# 03-ZYNQ_BANK_500.net
KiCad netlist of a schematic drawn in Altium Designer
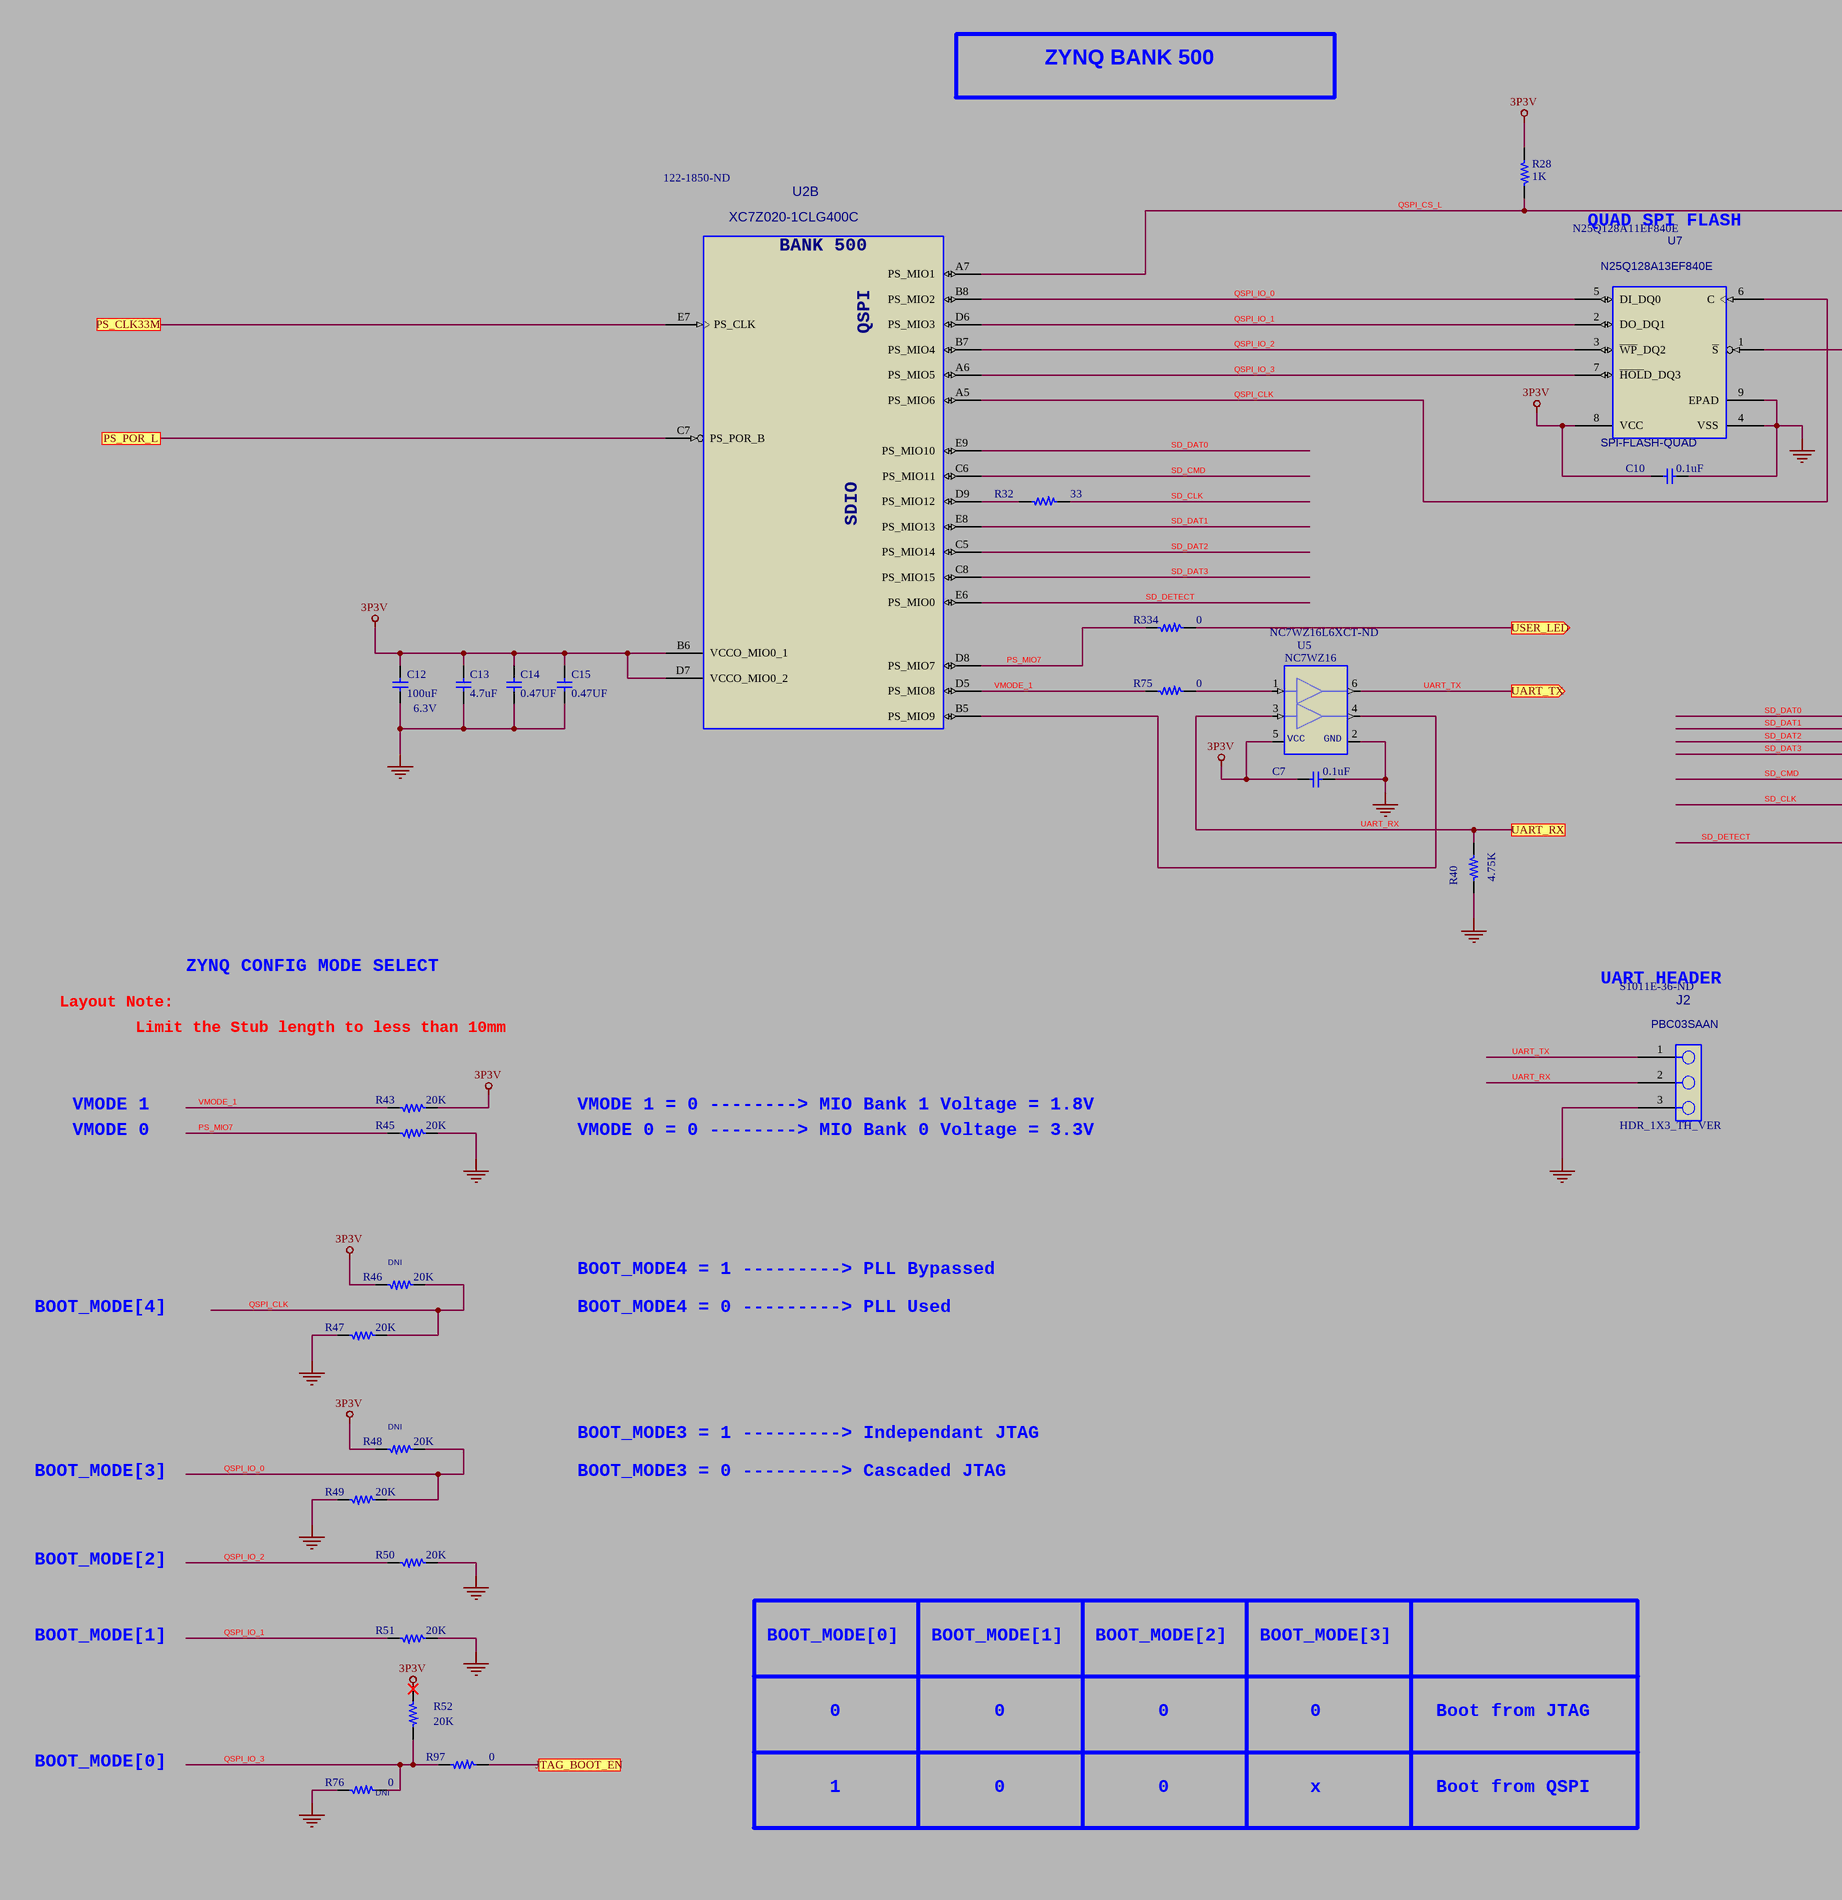
[diagram p0: 03-ZYNQ BANK 500.SchDoc, left]
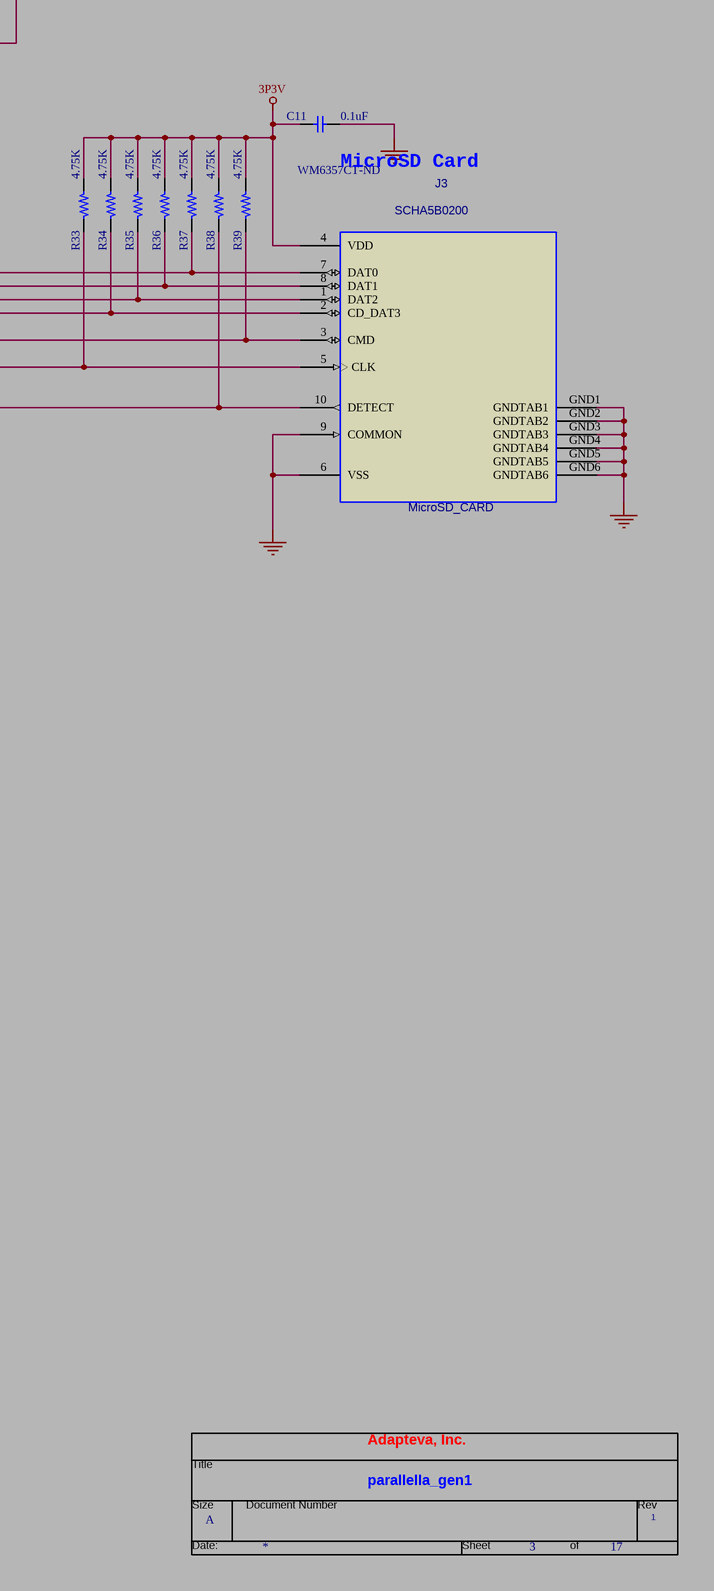
[diagram p1: 03-ZYNQ BANK 500.SchDoc, right]

(export (version "E")
  (design (tool "Eeschema 10.0.6"))
  (components
    (comp (ref "C7")
      (value "0.1uF")
      (footprint "C0402")
      (description "CAP, 0402, 0.1UF, X5R, 35V")
      (fields (field (name "MFG PART NO") "GMK105BJ104KV-F") (field (name "MFG") "TAIYO YUDEN"))
      (libsource (lib "*") (part "CAP0402_0P1UF_X5R_35V"))
    )
    (comp (ref "C10")
      (value "0.1uF")
      (footprint "C0402")
      (description "CAP, 0402, 0.1UF, X5R, 35V")
      (fields (field (name "MFG PART NO") "GMK105BJ104KV-F") (field (name "MFG") "TAIYO YUDEN"))
      (libsource (lib "*") (part "CAP0402_0P1UF_X5R_35V"))
    )
    (comp (ref "C11")
      (value "0.1uF")
      (footprint "C0402")
      (description "CAP, 0402, 0.1UF, X5R, 35V")
      (fields (field (name "MFG PART NO") "GMK105BJ104KV-F") (field (name "MFG") "TAIYO YUDEN"))
      (libsource (lib "*") (part "CAP0402_0P1UF_X5R_35V"))
    )
    (comp (ref "C12")
      (value "100uF")
      (footprint "C1210")
      (description "CAP, 1210, 100UF, X5R, 6.3V, LOW ESR")
      (fields
        (field (name "VOLTAGE") "6.3V")
        (field (name "MFG PART NO") "GRM32ER60J107ME20L")
        (field (name "MFG") "MURATA")
      )
      (libsource (lib "*") (part "CAP1210_100UF_X5R_LOESR"))
    )
    (comp (ref "C13")
      (value "4.7uF")
      (footprint "C0402")
      (description "CAP, 0402, 4.7UF, X5R, 6.3V")
      (fields (field (name "MFG PART NO") "C1005X5R0J475K") (field (name "MFG") "TDK"))
      (libsource (lib "*") (part "CAP0402_4P7UF_X5R"))
    )
    (comp (ref "C14")
      (value "0.47UF")
      (footprint "C0402")
      (description "CAP, 0402, 0.47UF, X5R, 16V")
      (fields (field (name "MFG") "TDK") (field (name "MFG PART NO") "C1005X5R1C474K"))
      (libsource (lib "*") (part "CAP0402_0P47UF_X5R"))
    )
    (comp (ref "C15")
      (value "0.47UF")
      (footprint "C0402")
      (description "CAP, 0402, 0.47UF, X5R, 16V")
      (fields (field (name "MFG") "TDK") (field (name "MFG PART NO") "C1005X5R1C474K"))
      (libsource (lib "*") (part "CAP0402_0P47UF_X5R"))
    )
    (comp (ref "J2")
      (value "HDR_1X3_TH_VER")
      (footprint "HDR_1X3_TH_VER")
      (description "HDR, 1ROW, 3POS, VERT, TH, 1X3, 0.100 PITCH")
      (fields
        (field (name "VENDOR PN") "PBC03SAAN")
        (field (name "MFG") "SULLINS")
        (field (name "MFG PART NO") "PBC36SAAN")
        (field (name "SUPPLIER PART NUMBER 1") "S1011E-36-ND")
      )
      (libsource (lib "*") (part "HDR_1X3_TH_VER_0.1P"))
    )
    (comp (ref "J3")
      (value "MicroSD_CARD")
      (footprint "SDMICRO_8PIN_REV_15SQX1P51MMH")
      (description "CONN, MICRO SD CARD, PUSH-PUSH")
      (fields
        (field (name "VENDOR PN") "SCHA5B0200")
        (field (name "MFG") "ALPS")
        (field (name "SUPPLIER PART NUMBER 1") "WM6357CT-ND")
      )
      (libsource (lib "*") (part "CONN_MICROSD_CARD"))
    )
    (comp (ref "R28")
      (value "1K")
      (footprint "R0402")
      (description "RES, 0402, 1K")
      (fields (field (name "MFG") "VISHAY") (field (name "MFG PART NO") "CRCW04021K00FKED"))
      (libsource (lib "*") (part "RES0402_1K"))
    )
    (comp (ref "R32")
      (value "33")
      (footprint "R0402")
      (description "RES, 0402, 33, 1%")
      (fields (field (name "MFG") "VISHAY") (field (name "MFG PART NO") "CRCW040233R0FKED"))
      (libsource (lib "*") (part "RES0402_33"))
    )
    (comp (ref "R33")
      (value "4.75K")
      (footprint "R0402")
      (description "RES, 0402, 4.75K, 1%")
      (fields (field (name "MFG") "VISHAY") (field (name "MFG PART NO") "CRCW04024K75FKED"))
      (libsource (lib "*") (part "RES0402_4K75"))
    )
    (comp (ref "R34")
      (value "4.75K")
      (footprint "R0402")
      (description "RES, 0402, 4.75K, 1%")
      (fields (field (name "MFG") "VISHAY") (field (name "MFG PART NO") "CRCW04024K75FKED"))
      (libsource (lib "*") (part "RES0402_4K75"))
    )
    (comp (ref "R35")
      (value "4.75K")
      (footprint "R0402")
      (description "RES, 0402, 4.75K, 1%")
      (fields (field (name "MFG") "VISHAY") (field (name "MFG PART NO") "CRCW04024K75FKED"))
      (libsource (lib "*") (part "RES0402_4K75"))
    )
    (comp (ref "R36")
      (value "4.75K")
      (footprint "R0402")
      (description "RES, 0402, 4.75K, 1%")
      (fields (field (name "MFG") "VISHAY") (field (name "MFG PART NO") "CRCW04024K75FKED"))
      (libsource (lib "*") (part "RES0402_4K75"))
    )
    (comp (ref "R37")
      (value "4.75K")
      (footprint "R0402")
      (description "RES, 0402, 4.75K, 1%")
      (fields (field (name "MFG") "VISHAY") (field (name "MFG PART NO") "CRCW04024K75FKED"))
      (libsource (lib "*") (part "RES0402_4K75"))
    )
    (comp (ref "R38")
      (value "4.75K")
      (footprint "R0402")
      (description "RES, 0402, 4.75K, 1%")
      (fields (field (name "MFG") "VISHAY") (field (name "MFG PART NO") "CRCW04024K75FKED"))
      (libsource (lib "*") (part "RES0402_4K75"))
    )
    (comp (ref "R39")
      (value "4.75K")
      (footprint "R0402")
      (description "RES, 0402, 4.75K, 1%")
      (fields (field (name "MFG") "VISHAY") (field (name "MFG PART NO") "CRCW04024K75FKED"))
      (libsource (lib "*") (part "RES0402_4K75"))
    )
    (comp (ref "R40")
      (value "4.75K")
      (footprint "R0402")
      (description "RES, 0402, 4.75K, 1%")
      (fields (field (name "MFG") "VISHAY") (field (name "MFG PART NO") "CRCW04024K75FKED"))
      (libsource (lib "*") (part "RES0402_4K75"))
    )
    (comp (ref "R43")
      (value "20K")
      (footprint "R0402")
      (description "RES, 0402, 20K")
      (fields (field (name "MFG PART NO") "CRCW040220K0FKED") (field (name "MFG") "VISHAY"))
      (libsource (lib "*") (part "RES0402_20K"))
    )
    (comp (ref "R45")
      (value "20K")
      (footprint "R0402")
      (description "RES, 0402, 20K")
      (fields (field (name "MFG PART NO") "CRCW040220K0FKED") (field (name "MFG") "VISHAY"))
      (libsource (lib "*") (part "RES0402_20K"))
    )
    (comp (ref "R46")
      (value "20K")
      (footprint "R0402")
      (description "RES, 0402, 20K")
      (fields
        (field (name "MFG PART NO") "CRCW040220K0FKED")
        (field (name "MFG") "VISHAY")
        (field (name "INSTALL") "DNI")
      )
      (libsource (lib "*") (part "RES0402_20K"))
    )
    (comp (ref "R47")
      (value "20K")
      (footprint "R0402")
      (description "RES, 0402, 20K")
      (fields (field (name "MFG PART NO") "CRCW040220K0FKED") (field (name "MFG") "VISHAY"))
      (libsource (lib "*") (part "RES0402_20K"))
    )
    (comp (ref "R48")
      (value "20K")
      (footprint "R0402")
      (description "RES, 0402, 20K")
      (fields
        (field (name "MFG PART NO") "CRCW040220K0FKED")
        (field (name "MFG") "VISHAY")
        (field (name "INSTALL") "DNI")
      )
      (libsource (lib "*") (part "RES0402_20K"))
    )
    (comp (ref "R49")
      (value "20K")
      (footprint "R0402")
      (description "RES, 0402, 20K")
      (fields (field (name "MFG PART NO") "CRCW040220K0FKED") (field (name "MFG") "VISHAY"))
      (libsource (lib "*") (part "RES0402_20K"))
    )
    (comp (ref "R50")
      (value "20K")
      (footprint "R0402")
      (description "RES, 0402, 20K")
      (fields (field (name "MFG PART NO") "CRCW040220K0FKED") (field (name "MFG") "VISHAY"))
      (libsource (lib "*") (part "RES0402_20K"))
    )
    (comp (ref "R51")
      (value "20K")
      (footprint "R0402")
      (description "RES, 0402, 20K")
      (fields (field (name "MFG PART NO") "CRCW040220K0FKED") (field (name "MFG") "VISHAY"))
      (libsource (lib "*") (part "RES0402_20K"))
    )
    (comp (ref "R52")
      (value "20K")
      (footprint "R0402")
      (description "RES, 0402, 20K")
      (fields (field (name "MFG PART NO") "CRCW040220K0FKED") (field (name "MFG") "VISHAY"))
      (libsource (lib "*") (part "RES0402_20K"))
    )
    (comp (ref "R75")
      (value "0")
      (footprint "R0402")
      (description "RES, 0402, 0 OHM, 1%")
      (fields (field (name "MFG") "VISHAY") (field (name "MFG PART NO") "CRCW04020000Z0ED"))
      (libsource (lib "*") (part "RES0402_0"))
    )
    (comp (ref "R76")
      (value "0")
      (footprint "R0402")
      (description "RES, 0402, 0 OHM, 1%")
      (fields
        (field (name "MFG") "VISHAY")
        (field (name "MFG PART NO") "CRCW04020000Z0ED")
        (field (name "INSTALL") "DNI")
      )
      (libsource (lib "*") (part "RES0402_0"))
    )
    (comp (ref "R97")
      (value "0")
      (footprint "R0402")
      (description "RES, 0402, 0 OHM, 1%")
      (fields (field (name "MFG") "VISHAY") (field (name "MFG PART NO") "CRCW04020000Z0ED"))
      (libsource (lib "*") (part "RES0402_0"))
    )
    (comp (ref "R334")
      (value "0")
      (footprint "R0402")
      (description "RES, 0402, 0 OHM, 1%")
      (fields (field (name "MFG") "VISHAY") (field (name "MFG PART NO") "CRCW04020000Z0ED"))
      (libsource (lib "*") (part "RES0402_0"))
    )
    (comp (ref "U2")
      (value "7Z020-CLG400")
      (footprint "CBGA400_17SQ_1P6H_P8MMP")
      (description "IC, EPP, XILINX, ZYNQ, 7Z020, CLG400")
      (fields
        (field (name "VENDOR PN") "XC7Z020-1CLG400C")
        (field (name "SUPPLIER PART NUMBER 1") "122-1850-ND")
      )
      (libsource (lib "*") (part "ZYNQ_7Z020_CLG400"))
    )
    (comp (ref "U5")
      (value "NC7WZ16")
      (footprint "SC_70_6PSMT")
      (fields
        (field (name "MFG PART NO") "NC7WZ16P6X")
        (field (name "MFG") "FAIRCHILD")
        (field (name "SUPPLIER PART NUMBER 1") "NC7WZ16L6XCT-ND")
      )
      (libsource (lib "*") (part "NC7WZ16"))
    )
    (comp (ref "U7")
      (value "SPI-FLASH-QUAD")
      (footprint "VPDFN-8_6X8XP85H_1P27MMP")
      (description "SPI FLASH, QUAD, 128M-BIT, VPDFN8, 1.8V")
      (fields
        (field (name "MFG") "MICRON")
        (field (name "MFG PART NO") "N25Q128A11EF840E")
        (field (name "VENDOR PN") "N25Q128A13EF840E")
        (field (name "SUPPLIER PART NUMBER 1") "N25Q128A11EF840E")
      )
      (libsource (lib "*") (part "IC_SPI_FLASH_QUAD_128Mb"))
    )
  )
  (nets
    (net (code "1") (name "/JTAG_BOOT_EN") (class "Default")
      (node (ref "R97") (pin "2") (pinfunction "2_2") (pintype "passive"))
    )
    (net (code "2") (name "/PS_CLK33M") (class "Default")
      (node (ref "U2") (pin "E7") (pinfunction "PS_CLK_E7") (pintype "input"))
    )
    (net (code "3") (name "/PS_MIO7") (class "Default")
      (node (ref "R334") (pin "1") (pinfunction "1_1") (pintype "passive"))
      (node (ref "R45") (pin "2") (pinfunction "2_2") (pintype "passive"))
      (node (ref "U2") (pin "D8") (pinfunction "PS_MIO7_D8") (pintype "bidirectional"))
    )
    (net (code "4") (name "/PS_POR_L") (class "Default")
      (node (ref "U2") (pin "C7") (pinfunction "PS_POR_B_C7") (pintype "input"))
    )
    (net (code "5") (name "/QSPI_CLK") (class "Default")
      (node (ref "R46") (pin "1") (pinfunction "1_1") (pintype "passive"))
      (node (ref "R47") (pin "1") (pinfunction "1_1") (pintype "passive"))
      (node (ref "U2") (pin "A5") (pinfunction "PS_MIO6_A5") (pintype "bidirectional"))
      (node (ref "U7") (pin "6") (pinfunction "C_6") (pintype "input"))
    )
    (net (code "6") (name "/QSPI_CS_L") (class "Default")
      (node (ref "R28") (pin "2") (pinfunction "2_2") (pintype "passive"))
      (node (ref "U2") (pin "A7") (pinfunction "PS_MIO1_A7") (pintype "bidirectional"))
      (node (ref "U7") (pin "1") (pinfunction "~{S}_1") (pintype "input"))
    )
    (net (code "7") (name "/QSPI_IO_0") (class "Default")
      (node (ref "R48") (pin "1") (pinfunction "1_1") (pintype "passive"))
      (node (ref "R49") (pin "1") (pinfunction "1_1") (pintype "passive"))
      (node (ref "U2") (pin "B8") (pinfunction "PS_MIO2_B8") (pintype "bidirectional"))
      (node (ref "U7") (pin "5") (pinfunction "DI_DQ0_5") (pintype "bidirectional"))
    )
    (net (code "8") (name "/QSPI_IO_1") (class "Default")
      (node (ref "R51") (pin "2") (pinfunction "2_2") (pintype "passive"))
      (node (ref "U2") (pin "D6") (pinfunction "PS_MIO3_D6") (pintype "bidirectional"))
      (node (ref "U7") (pin "2") (pinfunction "DO_DQ1_2") (pintype "bidirectional"))
    )
    (net (code "9") (name "/QSPI_IO_2") (class "Default")
      (node (ref "R50") (pin "2") (pinfunction "2_2") (pintype "passive"))
      (node (ref "U2") (pin "B7") (pinfunction "PS_MIO4_B7") (pintype "bidirectional"))
      (node (ref "U7") (pin "3") (pinfunction "~{WP}_DQ2_3") (pintype "bidirectional"))
    )
    (net (code "10") (name "/QSPI_IO_3") (class "Default")
      (node (ref "R52") (pin "2") (pinfunction "2_2") (pintype "passive"))
      (node (ref "R76") (pin "2") (pinfunction "2_2") (pintype "passive"))
      (node (ref "R97") (pin "1") (pinfunction "1_1") (pintype "passive"))
      (node (ref "U2") (pin "A6") (pinfunction "PS_MIO5_A6") (pintype "bidirectional"))
      (node (ref "U7") (pin "7") (pinfunction "~{HOL}D_DQ3_7") (pintype "bidirectional"))
    )
    (net (code "11") (name "/SD_CLK") (class "Default")
      (node (ref "J3") (pin "5") (pinfunction "CLK_5") (pintype "input"))
      (node (ref "R32") (pin "2") (pinfunction "2_2") (pintype "passive"))
      (node (ref "R33") (pin "1") (pinfunction "1_1") (pintype "passive"))
    )
    (net (code "12") (name "/SD_CMD") (class "Default")
      (node (ref "J3") (pin "3") (pinfunction "CMD_3") (pintype "bidirectional"))
      (node (ref "R39") (pin "1") (pinfunction "1_1") (pintype "passive"))
      (node (ref "U2") (pin "C6") (pinfunction "PS_MIO11_C6") (pintype "bidirectional"))
    )
    (net (code "13") (name "/SD_DAT0") (class "Default")
      (node (ref "J3") (pin "7") (pinfunction "DAT0_7") (pintype "bidirectional"))
      (node (ref "R37") (pin "1") (pinfunction "1_1") (pintype "passive"))
      (node (ref "U2") (pin "E9") (pinfunction "PS_MIO10_E9") (pintype "bidirectional"))
    )
    (net (code "14") (name "/SD_DAT1") (class "Default")
      (node (ref "J3") (pin "8") (pinfunction "DAT1_8") (pintype "bidirectional"))
      (node (ref "R36") (pin "1") (pinfunction "1_1") (pintype "passive"))
      (node (ref "U2") (pin "E8") (pinfunction "PS_MIO13_E8") (pintype "bidirectional"))
    )
    (net (code "15") (name "/SD_DAT2") (class "Default")
      (node (ref "J3") (pin "1") (pinfunction "DAT2_1") (pintype "bidirectional"))
      (node (ref "R35") (pin "1") (pinfunction "1_1") (pintype "passive"))
      (node (ref "U2") (pin "C5") (pinfunction "PS_MIO14_C5") (pintype "bidirectional"))
    )
    (net (code "16") (name "/SD_DAT3") (class "Default")
      (node (ref "J3") (pin "2") (pinfunction "CD_DAT3_2") (pintype "bidirectional"))
      (node (ref "R34") (pin "1") (pinfunction "1_1") (pintype "passive"))
      (node (ref "U2") (pin "C8") (pinfunction "PS_MIO15_C8") (pintype "bidirectional"))
    )
    (net (code "17") (name "/SD_DETECT") (class "Default")
      (node (ref "J3") (pin "10") (pinfunction "DETECT_10") (pintype "output"))
      (node (ref "R38") (pin "1") (pinfunction "1_1") (pintype "passive"))
      (node (ref "U2") (pin "E6") (pinfunction "PS_MIO0_E6") (pintype "bidirectional"))
    )
    (net (code "18") (name "/UART_RX") (class "Default")
      (node (ref "J2") (pin "2") (pinfunction "2_2") (pintype "passive"))
      (node (ref "R40") (pin "2") (pinfunction "2_2") (pintype "passive"))
      (node (ref "U5") (pin "3") (pinfunction "A2_3") (pintype "input"))
    )
    (net (code "19") (name "/UART_TX") (class "Default")
      (node (ref "J2") (pin "1") (pinfunction "1_1") (pintype "passive"))
      (node (ref "U5") (pin "6") (pinfunction "Y1_6") (pintype "output"))
    )
    (net (code "20") (name "/USER_LED") (class "Default")
      (node (ref "R334") (pin "2") (pinfunction "2_2") (pintype "passive"))
    )
    (net (code "21") (name "/VMODE_1") (class "Default")
      (node (ref "R43") (pin "2") (pinfunction "2_2") (pintype "passive"))
      (node (ref "R75") (pin "1") (pinfunction "1_1") (pintype "passive"))
      (node (ref "U2") (pin "D5") (pinfunction "PS_MIO8_D5") (pintype "bidirectional"))
    )
    (net (code "22") (name "3P3V") (class "Default")
      (node (ref "C10") (pin "2") (pinfunction "2_2") (pintype "passive"))
      (node (ref "C11") (pin "2") (pinfunction "2_2") (pintype "passive"))
      (node (ref "C12") (pin "1") (pinfunction "1_1") (pintype "passive"))
      (node (ref "C13") (pin "1") (pinfunction "1_1") (pintype "passive"))
      (node (ref "C14") (pin "1") (pinfunction "1_1") (pintype "passive"))
      (node (ref "C15") (pin "1") (pinfunction "1_1") (pintype "passive"))
      (node (ref "C7") (pin "2") (pinfunction "2_2") (pintype "passive"))
      (node (ref "J3") (pin "4") (pinfunction "VDD_4") (pintype "power_in"))
      (node (ref "R28") (pin "1") (pinfunction "1_1") (pintype "passive"))
      (node (ref "R33") (pin "2") (pinfunction "2_2") (pintype "passive"))
      (node (ref "R34") (pin "2") (pinfunction "2_2") (pintype "passive"))
      (node (ref "R35") (pin "2") (pinfunction "2_2") (pintype "passive"))
      (node (ref "R36") (pin "2") (pinfunction "2_2") (pintype "passive"))
      (node (ref "R37") (pin "2") (pinfunction "2_2") (pintype "passive"))
      (node (ref "R38") (pin "2") (pinfunction "2_2") (pintype "passive"))
      (node (ref "R39") (pin "2") (pinfunction "2_2") (pintype "passive"))
      (node (ref "R43") (pin "1") (pinfunction "1_1") (pintype "passive"))
      (node (ref "R46") (pin "2") (pinfunction "2_2") (pintype "passive"))
      (node (ref "R48") (pin "2") (pinfunction "2_2") (pintype "passive"))
      (node (ref "R52") (pin "1") (pinfunction "1_1") (pintype "passive"))
      (node (ref "U2") (pin "B6") (pinfunction "VCCO_MIO0_1_B6") (pintype "power_in"))
      (node (ref "U2") (pin "D7") (pinfunction "VCCO_MIO0_2_D7") (pintype "power_in"))
      (node (ref "U5") (pin "5") (pinfunction "VCC_5") (pintype "power_in"))
      (node (ref "U7") (pin "8") (pinfunction "VCC_8") (pintype "power_in"))
    )
    (net (code "23") (name "GND") (class "Default")
      (node (ref "C10") (pin "1") (pinfunction "1_1") (pintype "passive"))
      (node (ref "C11") (pin "1") (pinfunction "1_1") (pintype "passive"))
      (node (ref "C12") (pin "2") (pinfunction "2_2") (pintype "passive"))
      (node (ref "C13") (pin "2") (pinfunction "2_2") (pintype "passive"))
      (node (ref "C14") (pin "2") (pinfunction "2_2") (pintype "passive"))
      (node (ref "C15") (pin "2") (pinfunction "2_2") (pintype "passive"))
      (node (ref "C7") (pin "1") (pinfunction "1_1") (pintype "passive"))
      (node (ref "J2") (pin "3") (pinfunction "3_3") (pintype "passive"))
      (node (ref "J3") (pin "6") (pinfunction "VSS_6") (pintype "power_in"))
      (node (ref "J3") (pin "9") (pinfunction "COMMON_9") (pintype "input"))
      (node (ref "J3") (pin "GND1") (pinfunction "GNDTAB1_GND1") (pintype "power_in"))
      (node (ref "J3") (pin "GND2") (pinfunction "GNDTAB2_GND2") (pintype "power_in"))
      (node (ref "J3") (pin "GND3") (pinfunction "GNDTAB3_GND3") (pintype "power_in"))
      (node (ref "J3") (pin "GND4") (pinfunction "GNDTAB4_GND4") (pintype "power_in"))
      (node (ref "J3") (pin "GND5") (pinfunction "GNDTAB5_GND5") (pintype "power_in"))
      (node (ref "J3") (pin "GND6") (pinfunction "GNDTAB6_GND6") (pintype "passive"))
      (node (ref "R40") (pin "1") (pinfunction "1_1") (pintype "passive"))
      (node (ref "R45") (pin "1") (pinfunction "1_1") (pintype "passive"))
      (node (ref "R47") (pin "2") (pinfunction "2_2") (pintype "passive"))
      (node (ref "R49") (pin "2") (pinfunction "2_2") (pintype "passive"))
      (node (ref "R50") (pin "1") (pinfunction "1_1") (pintype "passive"))
      (node (ref "R51") (pin "1") (pinfunction "1_1") (pintype "passive"))
      (node (ref "R76") (pin "1") (pinfunction "1_1") (pintype "passive"))
      (node (ref "U5") (pin "2") (pinfunction "GND_2") (pintype "power_in"))
      (node (ref "U7") (pin "4") (pinfunction "VSS_4") (pintype "power_in"))
      (node (ref "U7") (pin "9") (pinfunction "EPAD_9") (pintype "power_in"))
    )
    (net (code "24") (name "Net-(U2B-PS_MIO9)") (class "Default")
      (node (ref "U2") (pin "B5") (pinfunction "PS_MIO9_B5") (pintype "bidirectional"))
      (node (ref "U5") (pin "4") (pinfunction "Y2_4") (pintype "output"))
    )
    (net (code "25") (name "Net-(U2B-PS_MIO12)") (class "Default")
      (node (ref "R32") (pin "1") (pinfunction "1_1") (pintype "passive"))
      (node (ref "U2") (pin "D9") (pinfunction "PS_MIO12_D9") (pintype "bidirectional"))
    )
    (net (code "26") (name "Net-(U5-A1)") (class "Default")
      (node (ref "R75") (pin "2") (pinfunction "2_2") (pintype "passive"))
      (node (ref "U5") (pin "1") (pinfunction "A1_1") (pintype "input"))
    )
  )
)
